# inamp.net
KiCad netlist of a schematic drawn in Altium Designer
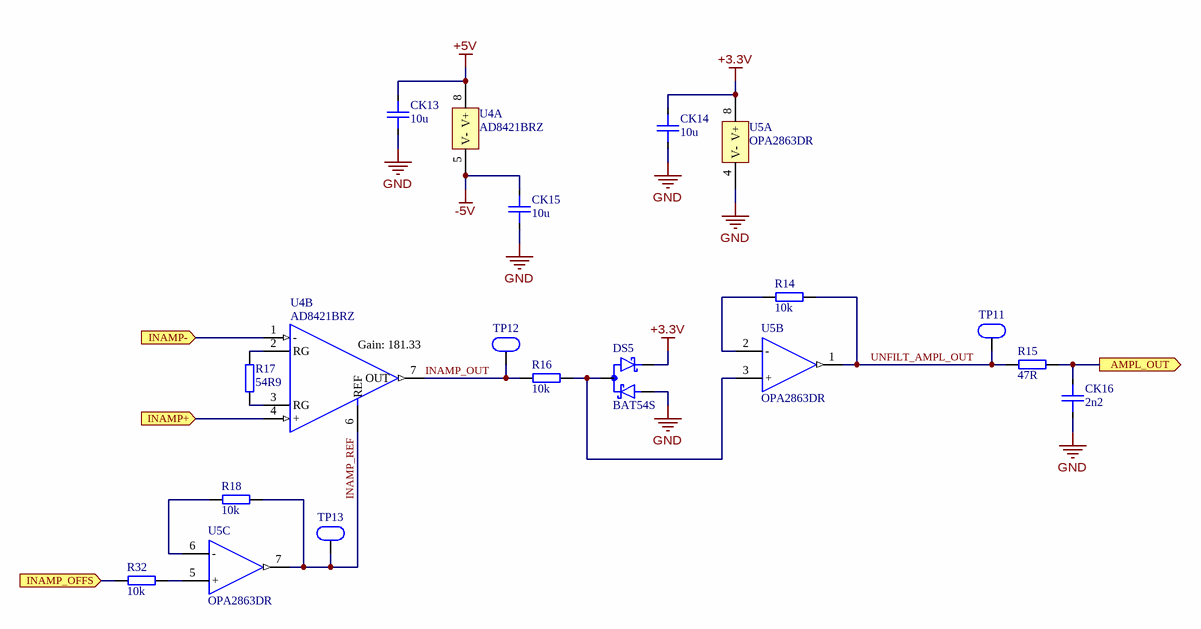
[diagram p0: inamp.SchDoc]

(export (version "E")
  (design (tool "Eeschema 10.0.6"))
  (components
    (comp (ref "CK13")
      (value "10u")
      (footprint "CAPC3225X27N(SMC1210)")
      (description "C; 10u; 50V; 10%; X7R; ??;")
      (fields
        (field (name "MANUFACTURER") "Murata: GRM32ER71H106KA12L;;Samsung Electro-mechanics: CL32B106KBJNNNE")
      )
      (libsource (lib "altium_sql") (part "CK"))
    )
    (comp (ref "CK14")
      (value "10u")
      (footprint "CAPC3225X27N(SMC1210)")
      (description "C; 10u; 50V; 10%; X7R; ??;")
      (fields
        (field (name "MANUFACTURER") "Murata: GRM32ER71H106KA12L;;Samsung Electro-mechanics: CL32B106KBJNNNE")
      )
      (libsource (lib "altium_sql") (part "CK"))
    )
    (comp (ref "CK15")
      (value "10u")
      (footprint "CAPC3225X27N(SMC1210)")
      (description "C; 10u; 50V; 10%; X7R; ??;")
      (fields
        (field (name "MANUFACTURER") "Murata: GRM32ER71H106KA12L;;Samsung Electro-mechanics: CL32B106KBJNNNE")
      )
      (libsource (lib "altium_sql") (part "CK"))
    )
    (comp (ref "CK16")
      (value "2n2")
      (footprint "CAPC2012X14N(SMC0805)")
      (description "C; 2n2; 50V; 5%; NP0/C0G; ??;")
      (fields
        (field (name "MANUFACTURER") "SAMSUNG: CL21C222JBFNNNE;;SAMSUNG: CL21C222JBFNNNF;;SAMSUNG: CL21C222JBFNNNG")
      )
      (libsource (lib "altium_sql") (part "CK"))
    )
    (comp (ref "DS5")
      (value "BAT54S")
      (footprint "SOT95P230X110-3N(SOT23)")
      (description "D; Schottky; 30V; 0.2A; 2x;")
      (fields
        (field (name "MANUFACTURER") "Diotec: BAT54S;;Philips: BAT54S,235;;FAI: BAT54S;;DIODES INC: BAT54S-7-F;;NXP: BAT54S,235")
      )
      (libsource (lib "altium_sql") (part "DDS"))
    )
    (comp (ref "R14")
      (value "10k")
      (footprint "RESC2012X06N(SMR0805)")
      (description "R; 10k; 0.125W; 1%; 150V; Thick Film; ±100ppm/K; 1x;")
      (libsource (lib "altium_sql") (part "R"))
    )
    (comp (ref "R15")
      (value "47R")
      (footprint "RESC2012X06N(SMR0805)")
      (description "R; 47R; 0.125W; 1%; 150V; Thick Film; ±100ppm/K; 1x;")
      (libsource (lib "altium_sql") (part "R"))
    )
    (comp (ref "R16")
      (value "10k")
      (footprint "RESC2012X06N(SMR0805)")
      (description "R; 10k; 0.125W; 1%; 150V; Thick Film; ±100ppm/K; 1x;")
      (libsource (lib "altium_sql") (part "R"))
    )
    (comp (ref "R17")
      (value "54R9")
      (footprint "RESC1608X06N(SMR0603)")
      (description "R; 54R9; 62.5mW; 0.1%; 50V; Thin Film; ±25ppm/K; 1x;")
      (libsource (lib "custom-footprints") (part "54R9"))
    )
    (comp (ref "R18")
      (value "10k")
      (footprint "RESC2012X06N(SMR0805)")
      (description "R; 10k; 0.125W; 1%; 150V; Thick Film; ±100ppm/K; 1x;")
      (libsource (lib "altium_sql") (part "R"))
    )
    (comp (ref "R32")
      (value "10k")
      (footprint "RESC2012X06N(SMR0805)")
      (description "R; 10k; 0.125W; 1%; 150V; Thick Film; ±100ppm/K; 1x;")
      (libsource (lib "altium_sql") (part "R"))
    )
    (comp (ref "TP11")
      (value "Test Point")
      (footprint "SMD_Testpoint_Onelayer")
      (description "Con; Test Point; 1x; PCB; ??; ??V; ??A; ??; Tin; Contact;")
      (fields (field (name "MANUFACTURER") "Harwin: S1751-46R") (field (name "CONNECTOR_PART") "Contact"))
      (libsource (lib "altium_sql") (part "EJ+TESTPOINTXX0"))
    )
    (comp (ref "TP12")
      (value "Test Point")
      (footprint "SMD_Testpoint_Onelayer")
      (description "Con; Test Point; 1x; PCB; ??; ??V; ??A; ??; Tin; Contact;")
      (fields (field (name "MANUFACTURER") "Harwin: S1751-46R") (field (name "CONNECTOR_PART") "Contact"))
      (libsource (lib "altium_sql") (part "EJ+TESTPOINTXX0"))
    )
    (comp (ref "TP13")
      (value "Test Point")
      (footprint "SMD_Testpoint_Onelayer")
      (description "Con; Test Point; 1x; PCB; ??; ??V; ??A; ??; Tin; Contact;")
      (fields (field (name "MANUFACTURER") "Harwin: S1751-46R") (field (name "CONNECTOR_PART") "Contact"))
      (libsource (lib "altium_sql") (part "EJ+TESTPOINTXX0"))
    )
    (comp (ref "U4")
      (value "AD8421BRZ")
      (footprint "SOIC127P600X175-8N(SOIC_8)")
      (description "High Performance, Low Power, Precision Instrumentation Amplifier")
      (libsource (lib "custom-footprints") (part "AD8421BRZ"))
    )
    (comp (ref "U5")
      (value "OPA2863DR")
      (footprint "SOIC127P600X175-8N(SOIC_8)")
      (description "IC; Opamp; 2.7V; 12.6V; 2x;")
      (fields (field (name "MANUFACTURER") "Texas Instruments: OPA2863DR"))
      (libsource (lib "altium_sql") (part "OP_AMP_DUAL_1"))
    )
  )
  (nets
    (net (code "1") (name "+3.3V") (class "Default")
      (node (ref "CK14") (pin "1") (pinfunction "1_1") (pintype "passive"))
      (node (ref "DS5") (pin "2") (pinfunction "C2_2") (pintype "passive"))
      (node (ref "U5") (pin "8") (pinfunction "V+_8") (pintype "power_in"))
    )
    (net (code "2") (name "+5V") (class "Default")
      (node (ref "CK13") (pin "1") (pinfunction "1_1") (pintype "passive"))
      (node (ref "U4") (pin "8") (pinfunction "V+_8") (pintype "power_in"))
    )
    (net (code "3") (name "-5V") (class "Default")
      (node (ref "CK15") (pin "1") (pinfunction "1_1") (pintype "passive"))
      (node (ref "U4") (pin "5") (pinfunction "V-_5") (pintype "passive"))
    )
    (net (code "4") (name "/AMPL_OUT") (class "Default")
      (node (ref "CK16") (pin "1") (pinfunction "1_1") (pintype "passive"))
      (node (ref "R15") (pin "1") (pinfunction "1_1") (pintype "passive"))
    )
    (net (code "5") (name "/INAMP+") (class "Default")
      (node (ref "U4") (pin "4") (pinfunction "+_4") (pintype "input"))
    )
    (net (code "6") (name "/INAMP-") (class "Default")
      (node (ref "U4") (pin "1") (pinfunction "-_1") (pintype "input"))
    )
    (net (code "7") (name "/INAMP_OFFS") (class "Default")
      (node (ref "R32") (pin "2") (pinfunction "2_2") (pintype "passive"))
    )
    (net (code "8") (name "/INAMP_OUT") (class "Default")
      (node (ref "R16") (pin "2") (pinfunction "2_2") (pintype "passive"))
      (node (ref "TP12") (pin "1") (pintype "passive"))
      (node (ref "U4") (pin "7") (pinfunction "OUT_7") (pintype "output"))
    )
    (net (code "9") (name "/INAMP_REF") (class "Default")
      (node (ref "R18") (pin "1") (pinfunction "1_1") (pintype "passive"))
      (node (ref "TP13") (pin "1") (pintype "passive"))
      (node (ref "U4") (pin "6") (pinfunction "REF_6") (pintype "passive"))
      (node (ref "U5") (pin "7") (pinfunction "OUT2_7") (pintype "output"))
    )
    (net (code "10") (name "/UNFILT_AMPL_OUT") (class "Default")
      (node (ref "R14") (pin "1") (pinfunction "1_1") (pintype "passive"))
      (node (ref "R15") (pin "2") (pinfunction "2_2") (pintype "passive"))
      (node (ref "TP11") (pin "1") (pintype "passive"))
      (node (ref "U5") (pin "1") (pinfunction "OUT1_1") (pintype "output"))
    )
    (net (code "11") (name "GND") (class "Default")
      (node (ref "CK13") (pin "2") (pinfunction "2_2") (pintype "passive"))
      (node (ref "CK14") (pin "2") (pinfunction "2_2") (pintype "passive"))
      (node (ref "CK15") (pin "2") (pinfunction "2_2") (pintype "passive"))
      (node (ref "CK16") (pin "2") (pinfunction "2_2") (pintype "passive"))
      (node (ref "DS5") (pin "1") (pinfunction "A1_1") (pintype "passive"))
      (node (ref "U5") (pin "4") (pinfunction "V-_4") (pintype "power_in"))
    )
    (net (code "12") (name "Net-(DS5-C1A2)") (class "Default")
      (node (ref "DS5") (pin "3") (pinfunction "C1A2_3") (pintype "passive"))
      (node (ref "R16") (pin "1") (pinfunction "1_1") (pintype "passive"))
      (node (ref "U5") (pin "3") (pinfunction "+_3") (pintype "passive"))
    )
    (net (code "13") (name "Net-(R17-Pad1)") (class "Default")
      (node (ref "R17") (pin "1") (pinfunction "1_1") (pintype "passive"))
      (node (ref "U4") (pin "3") (pinfunction "RG_3") (pintype "passive"))
    )
    (net (code "14") (name "Net-(R17-Pad2)") (class "Default")
      (node (ref "R17") (pin "2") (pinfunction "2_2") (pintype "passive"))
      (node (ref "U4") (pin "2") (pinfunction "RG_2") (pintype "passive"))
    )
    (net (code "15") (name "Net-(U5B--)") (class "Default")
      (node (ref "R14") (pin "2") (pinfunction "2_2") (pintype "passive"))
      (node (ref "U5") (pin "2") (pinfunction "-_2") (pintype "passive"))
    )
    (net (code "16") (name "Net-(U5C-+)") (class "Default")
      (node (ref "R32") (pin "1") (pinfunction "1_1") (pintype "passive"))
      (node (ref "U5") (pin "5") (pinfunction "+_5") (pintype "passive"))
    )
    (net (code "17") (name "Net-(U5C--)") (class "Default")
      (node (ref "R18") (pin "2") (pinfunction "2_2") (pintype "passive"))
      (node (ref "U5") (pin "6") (pinfunction "-_6") (pintype "passive"))
    )
  )
)
